# Transmissometer_RX_Boardv1.net
KiCad netlist of a schematic drawn in EAGLE
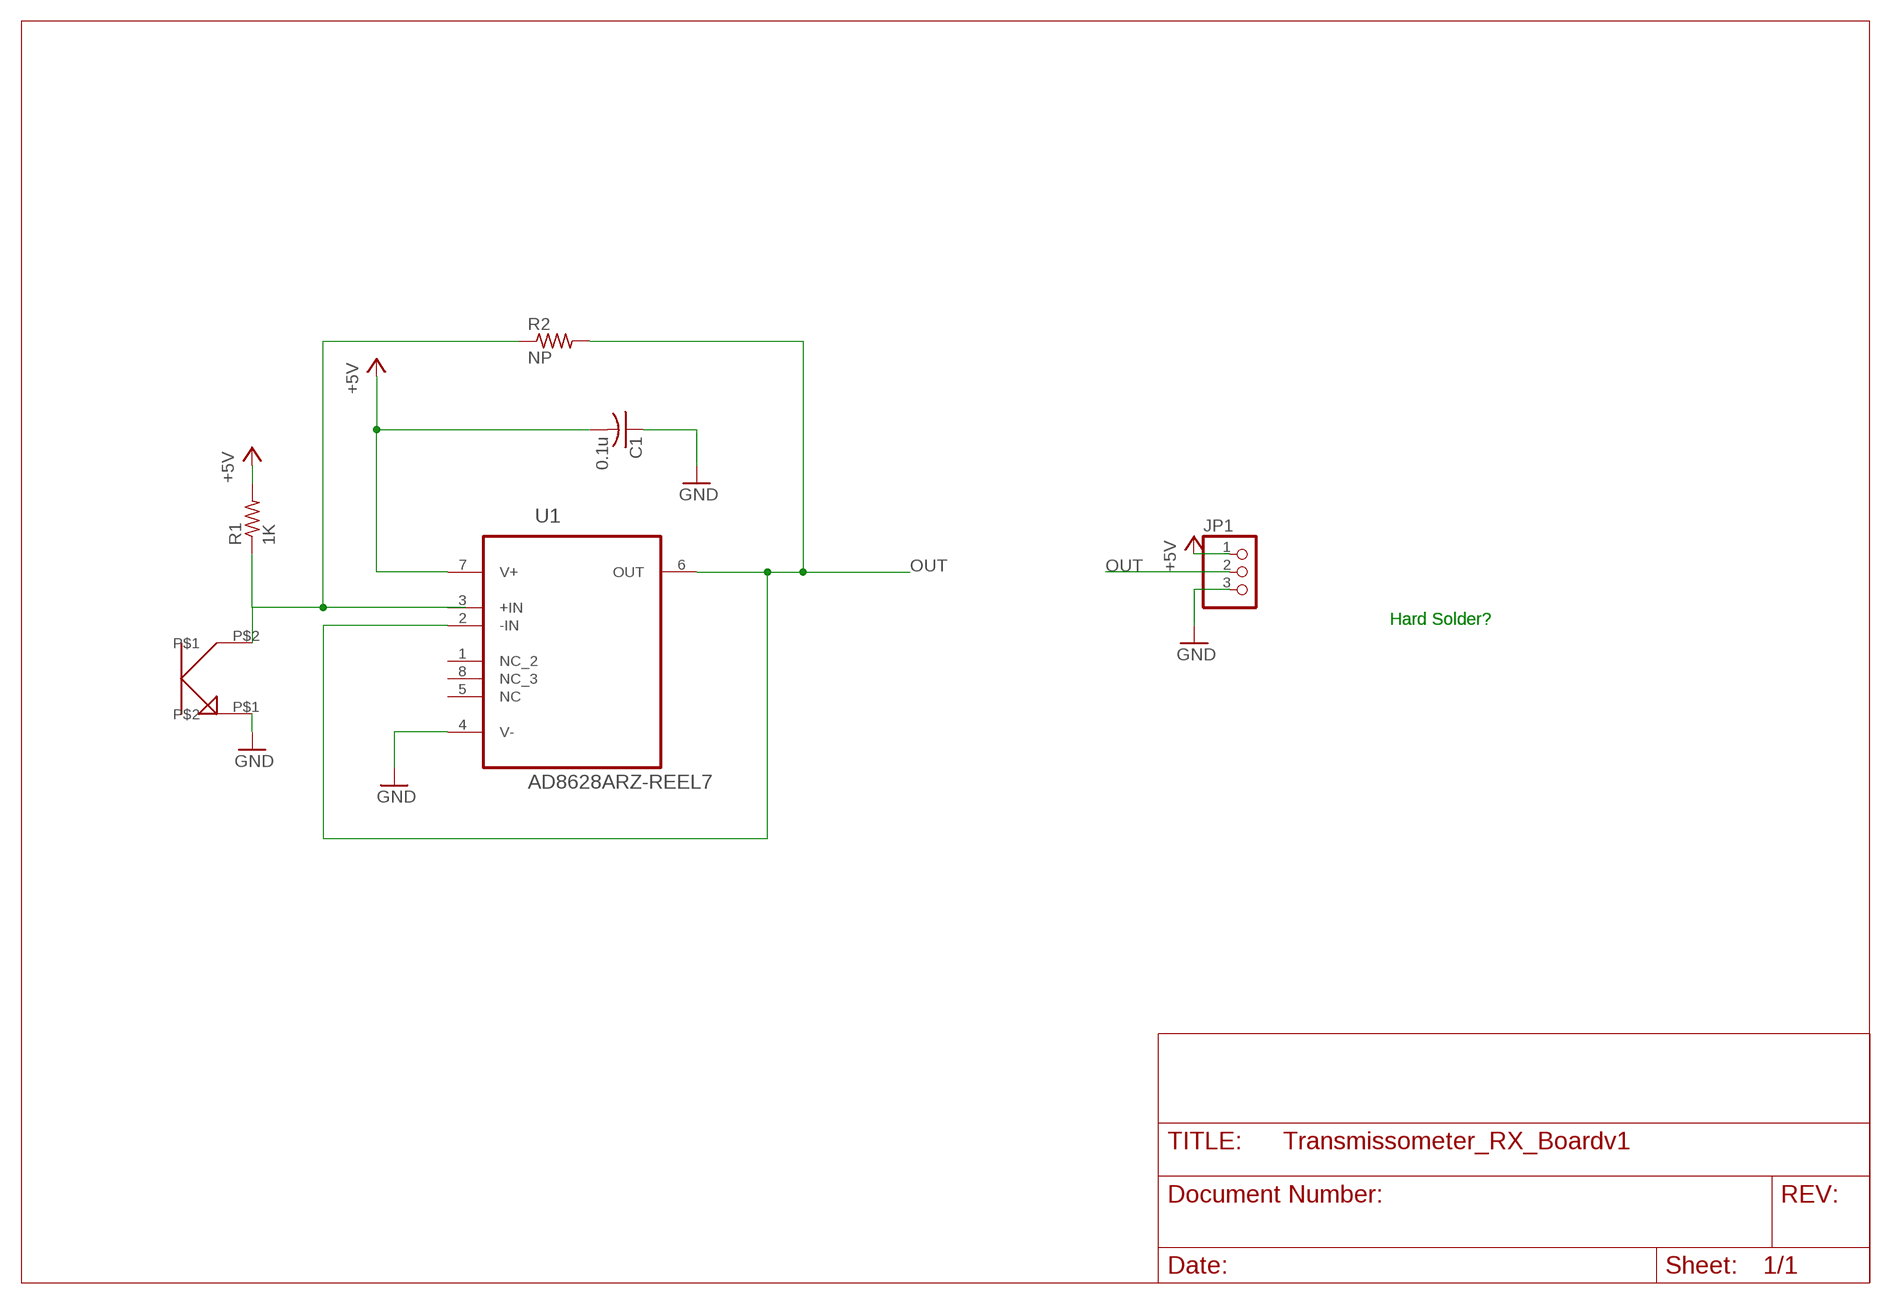
[diagram p0: schematic, sheet 1]

(export (version "E")
  (design (tool "Eeschema 10.0.6"))
  (components
    (comp (ref "C1")
      (value "0.1u")
      (footprint "eagle-import:C0805")
      (libsource (lib "eagle-import") (part "C-USC0805"))
    )
    (comp (ref "JP1")
      (value "PINHD-1X3")
      (footprint "eagle-import:1X03")
      (libsource (lib "eagle-import") (part "PINHD-1X3"))
    )
    (comp (ref "R1")
      (value "1K")
      (footprint "eagle-import:R0805")
      (libsource (lib "eagle-import") (part "R-US_R0805"))
    )
    (comp (ref "R2")
      (value "NP")
      (footprint "eagle-import:R0805")
      (libsource (lib "eagle-import") (part "R-US_R0805"))
    )
    (comp (ref "U$1")
      (value "TEMPT1020")
      (footprint "eagle-import:TEMPT1020")
      (libsource (lib "eagle-import") (part "TEMPT1020"))
    )
    (comp (ref "U1")
      (value "AD8628ARZ-REEL7")
      (footprint "eagle-import:SOIC127P600X175-8N")
      (libsource (lib "eagle-import") (part "AD8628ARZ-REEL7"))
    )
  )
  (nets
    (net (code "1") (name "+5V") (class "Default")
      (node (ref "C1") (pin "2") (pinfunction "2_2") (pintype "passive"))
      (node (ref "JP1") (pin "1") (pinfunction "1_1") (pintype "passive"))
      (node (ref "R1") (pin "2") (pinfunction "2_2") (pintype "passive"))
      (node (ref "U1") (pin "7") (pinfunction "V+_7") (pintype "power_in"))
    )
    (net (code "2") (name "/OUT") (class "Default")
      (node (ref "JP1") (pin "2") (pinfunction "2_2") (pintype "passive"))
      (node (ref "R2") (pin "2") (pinfunction "2_2") (pintype "passive"))
      (node (ref "U1") (pin "2") (pinfunction "-IN_2") (pintype "input"))
      (node (ref "U1") (pin "6") (pinfunction "OUT_6") (pintype "output"))
    )
    (net (code "3") (name "GND") (class "Default")
      (node (ref "C1") (pin "1") (pinfunction "1_1") (pintype "passive"))
      (node (ref "JP1") (pin "3") (pinfunction "3_3") (pintype "passive"))
      (node (ref "U$1") (pin "P$1") (pinfunction "P$2_P$1") (pintype "bidirectional"))
      (node (ref "U1") (pin "4") (pinfunction "V-_4") (pintype "power_in"))
    )
    (net (code "4") (name "Net-(U$1-P$1)") (class "Default")
      (node (ref "R1") (pin "1") (pinfunction "1_1") (pintype "passive"))
      (node (ref "R2") (pin "1") (pinfunction "1_1") (pintype "passive"))
      (node (ref "U$1") (pin "P$2") (pinfunction "P$1_P$2") (pintype "bidirectional"))
      (node (ref "U1") (pin "3") (pinfunction "+IN_3") (pintype "input"))
    )
    (net (code "5") (name "unconnected-(U1-NC-Pad5)") (class "Default")
      (node (ref "U1") (pin "5") (pinfunction "NC_5") (pintype "no_connect"))
    )
    (net (code "6") (name "unconnected-(U1-NC_2-Pad1)") (class "Default")
      (node (ref "U1") (pin "1") (pinfunction "NC_2_1") (pintype "no_connect"))
    )
    (net (code "7") (name "unconnected-(U1-NC_3-Pad8)") (class "Default")
      (node (ref "U1") (pin "8") (pinfunction "NC_3_8") (pintype "no_connect"))
    )
  )
)
